# Fiber_interlock.net
KiCad netlist of a schematic drawn in Altium Designer
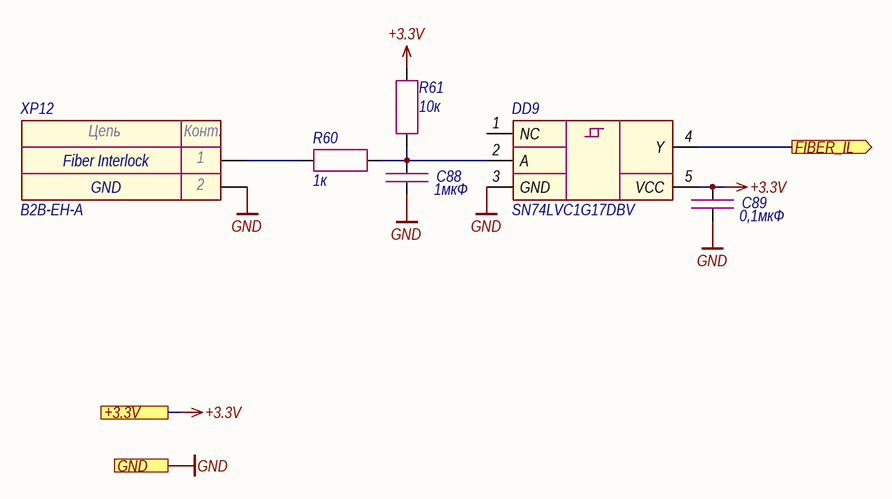
[diagram p0: Fiber_interlock.SchDoc]

(export (version "E")
  (design (tool "Eeschema 10.0.6"))
  (components
    (comp (ref "C88")
      (value "1мкФ")
      (footprint "Pcb_library:CAP_0603")
      (fields (field (name "MANUFACTURER") "Murata"))
      (libsource (lib "Schem_library") (part "Capacitor"))
    )
    (comp (ref "C89")
      (value "0,1мкФ")
      (footprint "Pcb_library:CAP_0603")
      (fields (field (name "MANUFACTURER") "Murata"))
      (libsource (lib "Schem_library") (part "Capacitor"))
    )
    (comp (ref "DD9")
      (value "SN74LVC1G17DBV")
      (footprint "Pcb_library:SOT-23-5")
      (fields (field (name "MANUFACTURER") "Texas Instruments"))
      (libsource (lib "Schem_library") (part "SN74LVC1G17"))
    )
    (comp (ref "R60")
      (value "1к")
      (footprint "Pcb_library:RES_0603")
      (fields (field (name "MANUFACTURER") "Yageo"))
      (libsource (lib "Schem_library") (part "Resistor"))
    )
    (comp (ref "R61")
      (value "10к")
      (footprint "Pcb_library:RES_0603")
      (fields (field (name "MANUFACTURER") "Yageo"))
      (libsource (lib "Schem_library") (part "Resistor"))
    )
    (comp (ref "XP12")
      (value "B2B-EH-A")
      (footprint "Pcb_library:B2B-EH-A")
      (fields (field (name "MANUFACTURER") "JST"))
      (libsource (lib "Schem_library") (part "Connector-2"))
    )
  )
  (nets
    (net (code "1") (name "+3.3V") (class "Default")
      (node (ref "C89") (pin "1") (pinfunction "1_1") (pintype "passive"))
      (node (ref "DD9") (pin "5") (pinfunction "VCC_5") (pintype "passive"))
      (node (ref "R61") (pin "2") (pinfunction "2_2") (pintype "passive"))
    )
    (net (code "2") (name "/FIBER_IL") (class "Default")
      (node (ref "DD9") (pin "4") (pinfunction "Y_4") (pintype "passive"))
    )
    (net (code "3") (name "GND") (class "Default")
      (node (ref "C88") (pin "2") (pinfunction "2_2") (pintype "passive"))
      (node (ref "C89") (pin "2") (pinfunction "2_2") (pintype "passive"))
      (node (ref "DD9") (pin "3") (pinfunction "GND_3") (pintype "passive"))
      (node (ref "XP12") (pin "2") (pintype "passive"))
    )
    (net (code "4") (name "Net-(DD9-A)") (class "Default")
      (node (ref "C88") (pin "1") (pinfunction "1_1") (pintype "passive"))
      (node (ref "DD9") (pin "2") (pinfunction "A_2") (pintype "passive"))
      (node (ref "R60") (pin "2") (pinfunction "2_2") (pintype "passive"))
      (node (ref "R61") (pin "1") (pinfunction "1_1") (pintype "passive"))
    )
    (net (code "5") (name "Net-(R60-Pad1)") (class "Default")
      (node (ref "R60") (pin "1") (pinfunction "1_1") (pintype "passive"))
      (node (ref "XP12") (pin "1") (pintype "passive"))
    )
    (net (code "6") (name "unconnected-(DD9-NC-Pad1)") (class "Default")
      (node (ref "DD9") (pin "1") (pinfunction "NC_1") (pintype "passive"))
    )
  )
)
